# smartWatch_Basic_TOP.net
KiCad netlist of a schematic drawn in EAGLE
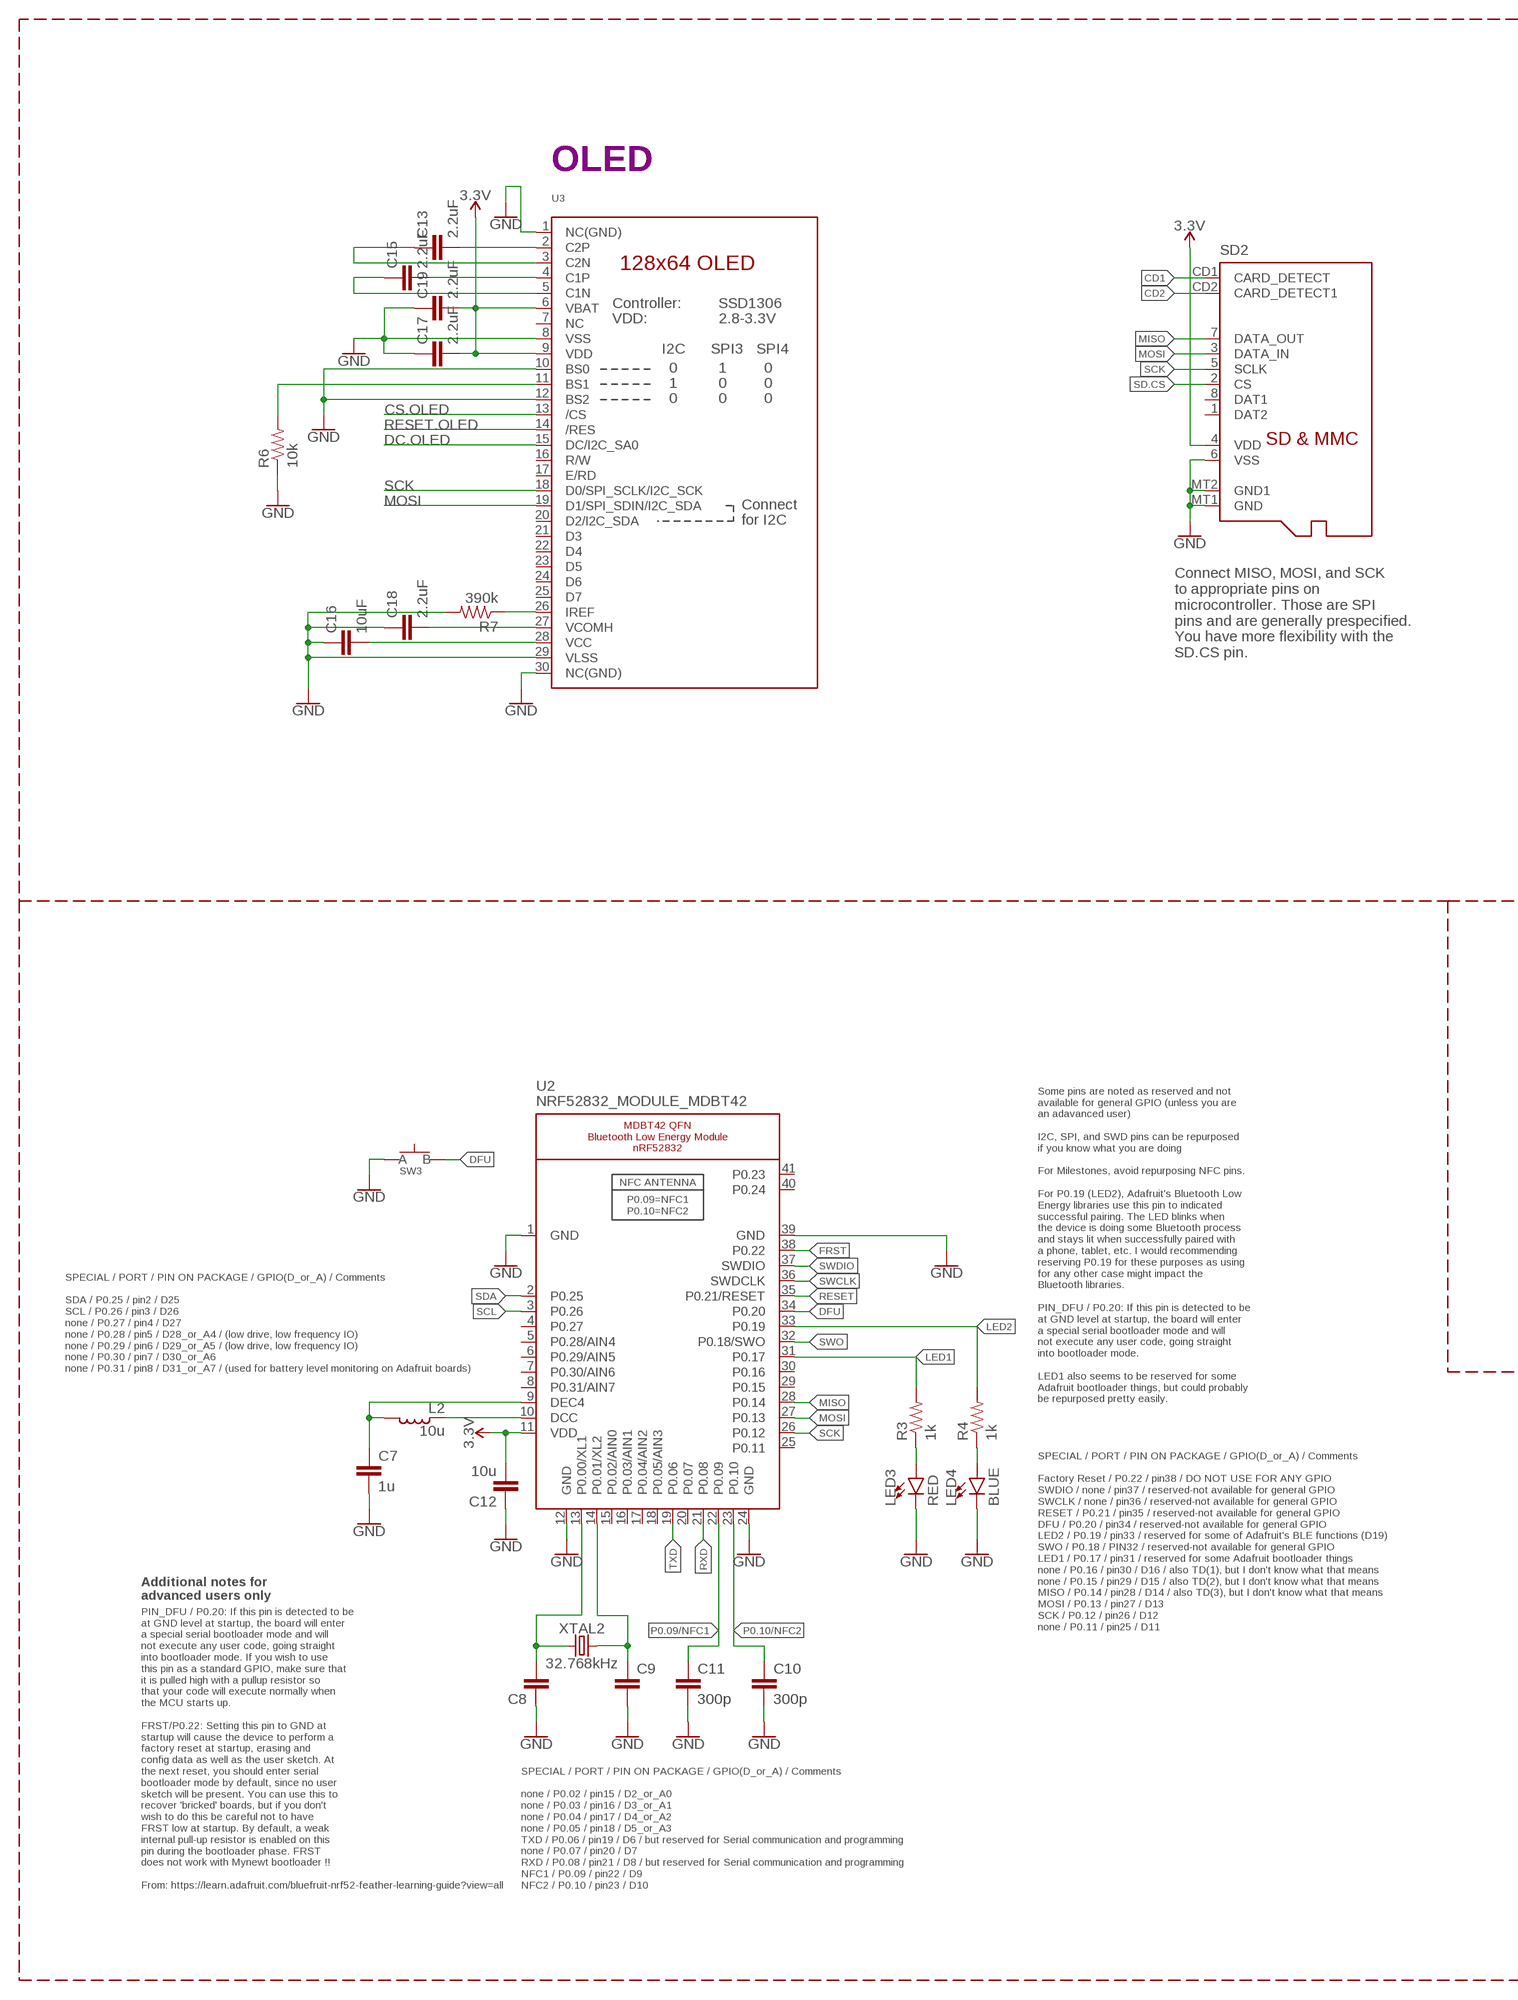
[diagram p0: schematic, sheet 1, part 1 of 2]
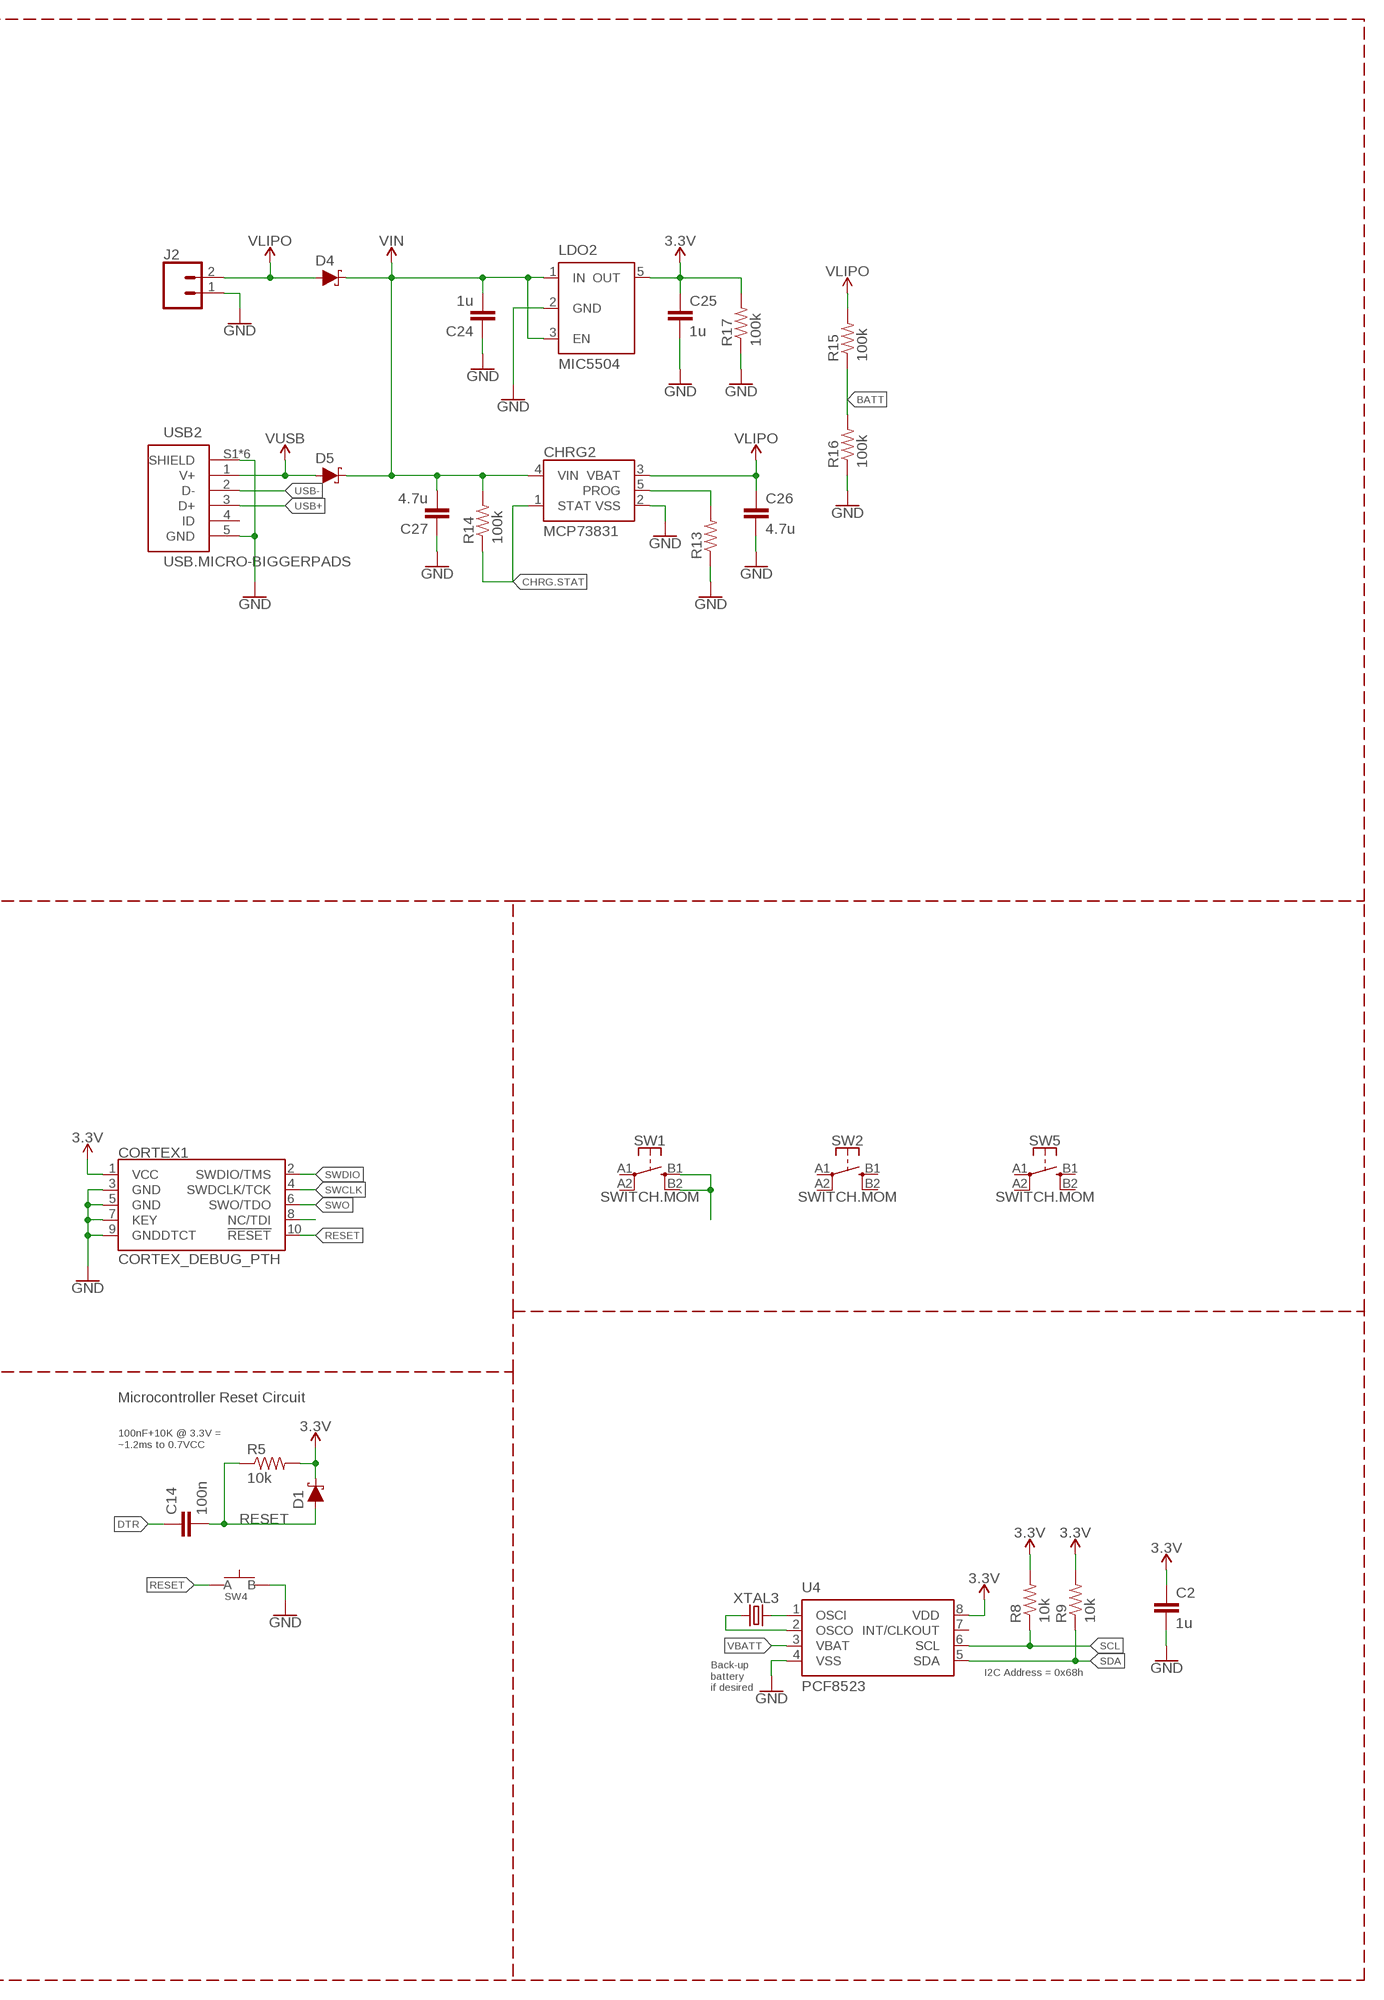
[diagram p1: schematic, sheet 1, part 2 of 2]

(export (version "E")
  (design (tool "Eeschema 10.0.6"))
  (components
    (comp (ref "C2")
      (value "1u")
      (footprint "eagle-import:C0603")
      (libsource (lib "eagle-import") (part "CAPACITOR0603"))
    )
    (comp (ref "C7")
      (value "1u")
      (footprint "eagle-import:C0603")
      (libsource (lib "eagle-import") (part "CAPACITOR0603"))
    )
    (comp (ref "C8")
      (value "CAPACITOR0603")
      (footprint "eagle-import:C0603")
      (libsource (lib "eagle-import") (part "CAPACITOR0603"))
    )
    (comp (ref "C9")
      (value "CAPACITOR0603")
      (footprint "eagle-import:C0603")
      (libsource (lib "eagle-import") (part "CAPACITOR0603"))
    )
    (comp (ref "C10")
      (value "300p")
      (footprint "eagle-import:C0603")
      (libsource (lib "eagle-import") (part "CAPACITOR0603"))
    )
    (comp (ref "C11")
      (value "300p")
      (footprint "eagle-import:C0603")
      (libsource (lib "eagle-import") (part "CAPACITOR0603"))
    )
    (comp (ref "C12")
      (value "10u")
      (footprint "eagle-import:C0805")
      (libsource (lib "eagle-import") (part "CAPACITOR0805"))
    )
    (comp (ref "C13")
      (value "2.2uF")
      (footprint "eagle-import:C0402")
      (libsource (lib "eagle-import") (part "CAPACITOR0402"))
    )
    (comp (ref "C14")
      (value "100n")
      (footprint "eagle-import:C0603")
      (libsource (lib "eagle-import") (part "CAPACITOR0603"))
    )
    (comp (ref "C15")
      (value "2.2uF")
      (footprint "eagle-import:C0402")
      (libsource (lib "eagle-import") (part "CAPACITOR0402"))
    )
    (comp (ref "C16")
      (value "10uF")
      (footprint "eagle-import:C0603")
      (libsource (lib "eagle-import") (part "CAPACITOR0603"))
    )
    (comp (ref "C17")
      (value "2.2uF")
      (footprint "eagle-import:C0402")
      (libsource (lib "eagle-import") (part "CAPACITOR0402"))
    )
    (comp (ref "C18")
      (value "2.2uF")
      (footprint "eagle-import:C0402")
      (libsource (lib "eagle-import") (part "CAPACITOR0402"))
    )
    (comp (ref "C19")
      (value "2.2uF")
      (footprint "eagle-import:C0402")
      (libsource (lib "eagle-import") (part "CAPACITOR0402"))
    )
    (comp (ref "C24")
      (value "1u")
      (footprint "eagle-import:C0603")
      (libsource (lib "eagle-import") (part "CAPACITOR0603"))
    )
    (comp (ref "C25")
      (value "1u")
      (footprint "eagle-import:C0603")
      (libsource (lib "eagle-import") (part "CAPACITOR0603"))
    )
    (comp (ref "C26")
      (value "4.7u")
      (footprint "eagle-import:C0603")
      (libsource (lib "eagle-import") (part "CAPACITOR0603"))
    )
    (comp (ref "C27")
      (value "4.7u")
      (footprint "eagle-import:C0603")
      (libsource (lib "eagle-import") (part "CAPACITOR0603"))
    )
    (comp (ref "CHRG2")
      (value "MCP73831")
      (footprint "eagle-import:SOT23-5")
      (libsource (lib "eagle-import") (part "MCP73831"))
    )
    (comp (ref "CORTEX1")
      (value "CORTEX_DEBUG_PTH")
      (footprint "eagle-import:2X5-PTH-1.27MM")
      (libsource (lib "eagle-import") (part "CORTEX_DEBUG_PTH"))
    )
    (comp (ref "D1")
      (value "SCHOTTKY-USC")
      (footprint "eagle-import:USC")
      (libsource (lib "eagle-import") (part "SCHOTTKY-USC"))
    )
    (comp (ref "D4")
      (value "SCHOTTKY-USC")
      (footprint "eagle-import:USC")
      (libsource (lib "eagle-import") (part "SCHOTTKY-USC"))
    )
    (comp (ref "D5")
      (value "SCHOTTKY-USC")
      (footprint "eagle-import:USC")
      (libsource (lib "eagle-import") (part "SCHOTTKY-USC"))
    )
    (comp (ref "J2")
      (value "CONN_02")
      (footprint "eagle-import:1X02")
      (libsource (lib "eagle-import") (part "CONN_02"))
    )
    (comp (ref "L2")
      (value "10u")
      (footprint "eagle-import:L0603")
      (libsource (lib "eagle-import") (part "INDUCTOR0603"))
    )
    (comp (ref "LDO2")
      (value "MIC5504")
      (footprint "eagle-import:SOT23-5")
      (libsource (lib "eagle-import") (part "MIC5504"))
    )
    (comp (ref "LED3")
      (value "RED")
      (footprint "eagle-import:LED-0603")
      (libsource (lib "eagle-import") (part "LED0603"))
    )
    (comp (ref "LED4")
      (value "BLUE")
      (footprint "eagle-import:LED-0603")
      (libsource (lib "eagle-import") (part "LED0603"))
    )
    (comp (ref "R3")
      (value "1k")
      (footprint "eagle-import:R0603")
      (libsource (lib "eagle-import") (part "RESISTOR0603"))
    )
    (comp (ref "R4")
      (value "1k")
      (footprint "eagle-import:R0603")
      (libsource (lib "eagle-import") (part "RESISTOR0603"))
    )
    (comp (ref "R5")
      (value "10k")
      (footprint "eagle-import:R0603")
      (libsource (lib "eagle-import") (part "RESISTOR0603"))
    )
    (comp (ref "R6")
      (value "10k")
      (footprint "eagle-import:R0603")
      (libsource (lib "eagle-import") (part "RESISTOR0603"))
    )
    (comp (ref "R7")
      (value "390k")
      (footprint "eagle-import:R0603")
      (libsource (lib "eagle-import") (part "RESISTOR0603"))
    )
    (comp (ref "R8")
      (value "10k")
      (footprint "eagle-import:R0603")
      (libsource (lib "eagle-import") (part "RESISTOR0603"))
    )
    (comp (ref "R9")
      (value "10k")
      (footprint "eagle-import:R0603")
      (libsource (lib "eagle-import") (part "RESISTOR0603"))
    )
    (comp (ref "R13")
      (value "RESISTOR0603")
      (footprint "eagle-import:R0603")
      (libsource (lib "eagle-import") (part "RESISTOR0603"))
    )
    (comp (ref "R14")
      (value "100k")
      (footprint "eagle-import:R0603")
      (libsource (lib "eagle-import") (part "RESISTOR0603"))
    )
    (comp (ref "R15")
      (value "100k")
      (footprint "eagle-import:R0603")
      (libsource (lib "eagle-import") (part "RESISTOR0603"))
    )
    (comp (ref "R16")
      (value "100k")
      (footprint "eagle-import:R0603")
      (libsource (lib "eagle-import") (part "RESISTOR0603"))
    )
    (comp (ref "R17")
      (value "100k")
      (footprint "eagle-import:R0603")
      (libsource (lib "eagle-import") (part "RESISTOR0603"))
    )
    (comp (ref "SD2")
      (value "MICROSD")
      (footprint "eagle-import:MICROSD")
      (libsource (lib "eagle-import") (part "MICROSD"))
    )
    (comp (ref "SW1")
      (value "SWITCH.MOM")
      (footprint "eagle-import:TACTILE_SWITCH_SMD_6.2MM_TALL")
      (libsource (lib "eagle-import") (part "SWITCH.MOM"))
    )
    (comp (ref "SW2")
      (value "SWITCH.MOM")
      (footprint "eagle-import:TACTILE_SWITCH_SMD_6.2MM_TALL")
      (libsource (lib "eagle-import") (part "SWITCH.MOM"))
    )
    (comp (ref "SW3")
      (value "SPST-PTS830GG140-COPY.1-3")
      (footprint "eagle-import:BUTTON-GULLWING")
      (libsource (lib "eagle-import") (part "SPST-PTS830GG140-COPY.1-3"))
    )
    (comp (ref "SW4")
      (value "SPST-PTS830GG140-COPY.1-3")
      (footprint "eagle-import:BUTTON-GULLWING")
      (libsource (lib "eagle-import") (part "SPST-PTS830GG140-COPY.1-3"))
    )
    (comp (ref "SW5")
      (value "SWITCH.MOM")
      (footprint "eagle-import:TACTILE_SWITCH_SMD_6.2MM_TALL")
      (libsource (lib "eagle-import") (part "SWITCH.MOM"))
    )
    (comp (ref "U2")
      (value "NRF52832_MODULE_MDBT42")
      (footprint "eagle-import:BLE_MODULE_RAYTAC_MDBT42")
      (libsource (lib "eagle-import") (part "NRF52832_MODULE_MDBT42"))
    )
    (comp (ref "U3")
      (value "DISP_OLED_UG-2864HSWEG01-NO-WRAPAROUND")
      (footprint "eagle-import:UG-2864HSWEG01_0.96IN_NO-WRAPAROUND")
      (libsource (lib "eagle-import") (part "DISP_OLED_UG-2864HSWEG01-NO-WRAPAROUND"))
    )
    (comp (ref "U4")
      (value "PCF8523")
      (footprint "eagle-import:SO8")
      (libsource (lib "eagle-import") (part "PCF8523"))
    )
    (comp (ref "USB2")
      (value "USB.MICRO-BIGGERPADS")
      (footprint "eagle-import:USB-MICRO-01.BIGGERPADS")
      (libsource (lib "eagle-import") (part "USB.MICRO-BIGGERPADS"))
    )
    (comp (ref "XTAL2")
      (value "32.768kHz")
      (footprint "eagle-import:2-SMD.NOLEAD.2.0MMTO1.2MM")
      (libsource (lib "eagle-import") (part "CRYSTALECS-.327-12.5-12-C-TR"))
    )
    (comp (ref "XTAL3")
      (value "32.7680kHz")
      (footprint "eagle-import:2-SMD.NOLEAD.2.0MMTO1.2MM")
      (fields (field (name "FREQ") "32.7680KHZ"))
      (libsource (lib "eagle-import") (part "CRYSTALECS-.327-12.5-12-C-TR"))
    )
  )
  (nets
    (net (code "1") (name "/CS.OLED") (class "Default")
      (node (ref "U3") (pin "13") (pinfunction "/CS_13") (pintype "input"))
    )
    (net (code "2") (name "/DC.OLED") (class "Default")
      (node (ref "U3") (pin "15") (pinfunction "DC/I2C_SA0_15") (pintype "input"))
    )
    (net (code "3") (name "/RESET.OLED") (class "Default")
      (node (ref "U3") (pin "14") (pinfunction "/RES_14") (pintype "input"))
    )
    (net (code "4") (name "3.3V") (class "Default")
      (node (ref "C12") (pin "2") (pinfunction "2_2") (pintype "passive"))
      (node (ref "C17") (pin "2") (pinfunction "2_2") (pintype "passive"))
      (node (ref "C19") (pin "2") (pinfunction "2_2") (pintype "passive"))
      (node (ref "C2") (pin "1") (pinfunction "1_1") (pintype "passive"))
      (node (ref "C25") (pin "1") (pinfunction "1_1") (pintype "passive"))
      (node (ref "CORTEX1") (pin "1") (pinfunction "VCC_1") (pintype "bidirectional"))
      (node (ref "D1") (pin "-") (pinfunction "C_-") (pintype "passive"))
      (node (ref "LDO2") (pin "5") (pinfunction "OUT_5") (pintype "bidirectional"))
      (node (ref "R17") (pin "2") (pinfunction "2_2") (pintype "passive"))
      (node (ref "R5") (pin "2") (pinfunction "2_2") (pintype "passive"))
      (node (ref "R8") (pin "2") (pinfunction "2_2") (pintype "passive"))
      (node (ref "R9") (pin "2") (pinfunction "2_2") (pintype "passive"))
      (node (ref "SD2") (pin "4") (pinfunction "VDD_4") (pintype "power_in"))
      (node (ref "U2") (pin "11") (pinfunction "VDD_11") (pintype "bidirectional"))
      (node (ref "U3") (pin "6") (pinfunction "VBAT_6") (pintype "input"))
      (node (ref "U3") (pin "9") (pinfunction "VDD_9") (pintype "power_in"))
      (node (ref "U4") (pin "8") (pinfunction "VDD_8") (pintype "power_in"))
    )
    (net (code "5") (name "BATT") (class "Default")
      (node (ref "R15") (pin "1") (pinfunction "1_1") (pintype "passive"))
      (node (ref "R16") (pin "2") (pinfunction "2_2") (pintype "passive"))
    )
    (net (code "6") (name "CD1") (class "Default")
      (node (ref "SD2") (pin "CD1") (pinfunction "CARD_DETECT_CD1") (pintype "passive"))
    )
    (net (code "7") (name "CD2") (class "Default")
      (node (ref "SD2") (pin "CD2") (pinfunction "CARD_DETECT1_CD2") (pintype "passive"))
    )
    (net (code "8") (name "CHRG.STAT") (class "Default")
      (node (ref "CHRG2") (pin "1") (pinfunction "STAT_1") (pintype "output"))
      (node (ref "R14") (pin "1") (pinfunction "1_1") (pintype "passive"))
    )
    (net (code "9") (name "DFU") (class "Default")
      (node (ref "SW3") (pin "3") (pinfunction "B_3") (pintype "bidirectional"))
      (node (ref "U2") (pin "34") (pinfunction "P0.20_34") (pintype "bidirectional"))
    )
    (net (code "10") (name "DTR") (class "Default")
      (node (ref "C14") (pin "1") (pinfunction "1_1") (pintype "passive"))
    )
    (net (code "11") (name "FRST") (class "Default")
      (node (ref "U2") (pin "38") (pinfunction "P0.22_38") (pintype "bidirectional"))
    )
    (net (code "12") (name "GND") (class "Default")
      (node (ref "C10") (pin "2") (pinfunction "2_2") (pintype "passive"))
      (node (ref "C11") (pin "2") (pinfunction "2_2") (pintype "passive"))
      (node (ref "C12") (pin "1") (pinfunction "1_1") (pintype "passive"))
      (node (ref "C16") (pin "1") (pinfunction "1_1") (pintype "passive"))
      (node (ref "C17") (pin "1") (pinfunction "1_1") (pintype "passive"))
      (node (ref "C18") (pin "1") (pinfunction "1_1") (pintype "passive"))
      (node (ref "C19") (pin "1") (pinfunction "1_1") (pintype "passive"))
      (node (ref "C2") (pin "2") (pinfunction "2_2") (pintype "passive"))
      (node (ref "C24") (pin "1") (pinfunction "1_1") (pintype "passive"))
      (node (ref "C25") (pin "2") (pinfunction "2_2") (pintype "passive"))
      (node (ref "C26") (pin "2") (pinfunction "2_2") (pintype "passive"))
      (node (ref "C27") (pin "1") (pinfunction "1_1") (pintype "passive"))
      (node (ref "C7") (pin "2") (pinfunction "2_2") (pintype "passive"))
      (node (ref "C8") (pin "1") (pinfunction "1_1") (pintype "passive"))
      (node (ref "C9") (pin "2") (pinfunction "2_2") (pintype "passive"))
      (node (ref "CHRG2") (pin "2") (pinfunction "VSS_2") (pintype "power_in"))
      (node (ref "CORTEX1") (pin "3") (pinfunction "GND_3") (pintype "bidirectional"))
      (node (ref "CORTEX1") (pin "5") (pinfunction "GND_5") (pintype "bidirectional"))
      (node (ref "CORTEX1") (pin "7") (pinfunction "KEY_7") (pintype "bidirectional"))
      (node (ref "CORTEX1") (pin "9") (pinfunction "GNDDTCT_9") (pintype "bidirectional"))
      (node (ref "J2") (pin "1") (pinfunction "1_1") (pintype "passive"))
      (node (ref "LDO2") (pin "2") (pinfunction "GND_2") (pintype "bidirectional"))
      (node (ref "LED3") (pin "C") (pinfunction "C_C") (pintype "passive"))
      (node (ref "LED4") (pin "C") (pinfunction "C_C") (pintype "passive"))
      (node (ref "R13") (pin "1") (pinfunction "1_1") (pintype "passive"))
      (node (ref "R16") (pin "1") (pinfunction "1_1") (pintype "passive"))
      (node (ref "R17") (pin "1") (pinfunction "1_1") (pintype "passive"))
      (node (ref "R6") (pin "1") (pinfunction "1_1") (pintype "passive"))
      (node (ref "R7") (pin "2") (pinfunction "2_2") (pintype "passive"))
      (node (ref "SD2") (pin "6") (pinfunction "VSS_6") (pintype "power_in"))
      (node (ref "SD2") (pin "MT1") (pinfunction "GND_MT1") (pintype "power_in"))
      (node (ref "SD2") (pin "MT2") (pinfunction "GND1_MT2") (pintype "power_in"))
      (node (ref "SW3") (pin "1") (pinfunction "A_1") (pintype "bidirectional"))
      (node (ref "SW4") (pin "3") (pinfunction "B_3") (pintype "bidirectional"))
      (node (ref "U2") (pin "1") (pinfunction "GND_1") (pintype "bidirectional"))
      (node (ref "U2") (pin "12") (pinfunction "GND_12") (pintype "bidirectional"))
      (node (ref "U2") (pin "24") (pinfunction "GND_24") (pintype "bidirectional"))
      (node (ref "U2") (pin "39") (pinfunction "GND_39") (pintype "bidirectional"))
      (node (ref "U3") (pin "1") (pinfunction "NC(GND)_1") (pintype "input"))
      (node (ref "U3") (pin "10") (pinfunction "BS0_10") (pintype "input"))
      (node (ref "U3") (pin "12") (pinfunction "BS2_12") (pintype "input"))
      (node (ref "U3") (pin "29") (pinfunction "VLSS_29") (pintype "power_in"))
      (node (ref "U3") (pin "30") (pinfunction "NC(GND)_30") (pintype "input"))
      (node (ref "U3") (pin "8") (pinfunction "VSS_8") (pintype "power_in"))
      (node (ref "U4") (pin "4") (pinfunction "VSS_4") (pintype "power_in"))
      (node (ref "USB2") (pin "5") (pinfunction "GND_5") (pintype "bidirectional"))
      (node (ref "USB2") (pin "S1") (pinfunction "SHIELD_S1") (pintype "bidirectional"))
      (node (ref "USB2") (pin "S2") (pinfunction "SHIELD_S2") (pintype "bidirectional"))
      (node (ref "USB2") (pin "S3") (pinfunction "SHIELD_S3") (pintype "bidirectional"))
      (node (ref "USB2") (pin "S4") (pinfunction "SHIELD_S4") (pintype "bidirectional"))
      (node (ref "USB2") (pin "S5") (pinfunction "SHIELD_S5") (pintype "bidirectional"))
      (node (ref "USB2") (pin "S6") (pinfunction "SHIELD_S6") (pintype "bidirectional"))
    )
    (net (code "13") (name "LED1") (class "Default")
      (node (ref "R3") (pin "2") (pinfunction "2_2") (pintype "passive"))
      (node (ref "U2") (pin "31") (pinfunction "P0.17_31") (pintype "bidirectional"))
    )
    (net (code "14") (name "LED2") (class "Default")
      (node (ref "R4") (pin "2") (pinfunction "2_2") (pintype "passive"))
      (node (ref "U2") (pin "33") (pinfunction "P0.19_33") (pintype "bidirectional"))
    )
    (net (code "15") (name "MISO") (class "Default")
      (node (ref "SD2") (pin "7") (pinfunction "DATA_OUT_7") (pintype "output"))
      (node (ref "U2") (pin "28") (pinfunction "P0.14_28") (pintype "bidirectional"))
    )
    (net (code "16") (name "MOSI") (class "Default")
      (node (ref "SD2") (pin "3") (pinfunction "DATA_IN_3") (pintype "input"))
      (node (ref "U2") (pin "27") (pinfunction "P0.13_27") (pintype "bidirectional"))
      (node (ref "U3") (pin "19") (pinfunction "D1/SPI_SDIN/I2C_SDA_19") (pintype "bidirectional"))
    )
    (net (code "17") (name "Net-(CHRG2-PROG)") (class "Default")
      (node (ref "CHRG2") (pin "5") (pinfunction "PROG_5") (pintype "input"))
      (node (ref "R13") (pin "2") (pinfunction "2_2") (pintype "passive"))
    )
    (net (code "18") (name "Net-(LED3-PadA)") (class "Default")
      (node (ref "LED3") (pin "A") (pinfunction "A_A") (pintype "passive"))
      (node (ref "R3") (pin "1") (pinfunction "1_1") (pintype "passive"))
    )
    (net (code "19") (name "Net-(LED4-PadA)") (class "Default")
      (node (ref "LED4") (pin "A") (pinfunction "A_A") (pintype "passive"))
      (node (ref "R4") (pin "1") (pinfunction "1_1") (pintype "passive"))
    )
    (net (code "20") (name "Net-(SW1-3)") (class "Default")
      (node (ref "SW1") (pin "B1") (pinfunction "3_B1") (pintype "passive"))
      (node (ref "SW1") (pin "B2") (pinfunction "4_B2") (pintype "passive"))
    )
    (net (code "21") (name "Net-(U2-DCC)") (class "Default")
      (node (ref "L2") (pin "1") (pinfunction "1_1") (pintype "passive"))
      (node (ref "U2") (pin "10") (pinfunction "DCC_10") (pintype "bidirectional"))
    )
    (net (code "22") (name "Net-(U2-DEC4)") (class "Default")
      (node (ref "C7") (pin "1") (pinfunction "1_1") (pintype "passive"))
      (node (ref "L2") (pin "2") (pinfunction "2_2") (pintype "passive"))
      (node (ref "U2") (pin "9") (pinfunction "DEC4_9") (pintype "bidirectional"))
    )
    (net (code "23") (name "Net-(U2-P0.00{slash}XL1)") (class "Default")
      (node (ref "C8") (pin "2") (pinfunction "2_2") (pintype "passive"))
      (node (ref "U2") (pin "13") (pinfunction "P0.00/XL1_13") (pintype "bidirectional"))
      (node (ref "XTAL2") (pin "P$1") (pinfunction "1_P$1") (pintype "passive"))
    )
    (net (code "24") (name "Net-(U2-P0.01{slash}XL2)") (class "Default")
      (node (ref "C9") (pin "1") (pinfunction "1_1") (pintype "passive"))
      (node (ref "U2") (pin "14") (pinfunction "P0.01/XL2_14") (pintype "bidirectional"))
      (node (ref "XTAL2") (pin "P$2") (pinfunction "2_P$2") (pintype "passive"))
    )
    (net (code "25") (name "Net-(U3-BS1)") (class "Default")
      (node (ref "R6") (pin "2") (pinfunction "2_2") (pintype "passive"))
      (node (ref "U3") (pin "11") (pinfunction "BS1_11") (pintype "input"))
    )
    (net (code "26") (name "Net-(U3-C1N)") (class "Default")
      (node (ref "C15") (pin "1") (pinfunction "1_1") (pintype "passive"))
      (node (ref "U3") (pin "5") (pinfunction "C1N_5") (pintype "input"))
    )
    (net (code "27") (name "Net-(U3-C1P)") (class "Default")
      (node (ref "C15") (pin "2") (pinfunction "2_2") (pintype "passive"))
      (node (ref "U3") (pin "4") (pinfunction "C1P_4") (pintype "input"))
    )
    (net (code "28") (name "Net-(U3-C2N)") (class "Default")
      (node (ref "C13") (pin "1") (pinfunction "1_1") (pintype "passive"))
      (node (ref "U3") (pin "3") (pinfunction "C2N_3") (pintype "input"))
    )
    (net (code "29") (name "Net-(U3-C2P)") (class "Default")
      (node (ref "C13") (pin "2") (pinfunction "2_2") (pintype "passive"))
      (node (ref "U3") (pin "2") (pinfunction "C2P_2") (pintype "input"))
    )
    (net (code "30") (name "Net-(U3-IREF)") (class "Default")
      (node (ref "R7") (pin "1") (pinfunction "1_1") (pintype "passive"))
      (node (ref "U3") (pin "26") (pinfunction "IREF_26") (pintype "input"))
    )
    (net (code "31") (name "Net-(U3-VCC)") (class "Default")
      (node (ref "C16") (pin "2") (pinfunction "2_2") (pintype "passive"))
      (node (ref "U3") (pin "28") (pinfunction "VCC_28") (pintype "power_in"))
    )
    (net (code "32") (name "Net-(U3-VCOMH)") (class "Default")
      (node (ref "C18") (pin "2") (pinfunction "2_2") (pintype "passive"))
      (node (ref "U3") (pin "27") (pinfunction "VCOMH_27") (pintype "output"))
    )
    (net (code "33") (name "Net-(U4-OSCI)") (class "Default")
      (node (ref "U4") (pin "1") (pinfunction "OSCI_1") (pintype "bidirectional"))
      (node (ref "XTAL3") (pin "P$2") (pinfunction "2_P$2") (pintype "passive"))
    )
    (net (code "34") (name "Net-(U4-OSCO)") (class "Default")
      (node (ref "U4") (pin "2") (pinfunction "OSCO_2") (pintype "bidirectional"))
      (node (ref "XTAL3") (pin "P$1") (pinfunction "1_P$1") (pintype "passive"))
    )
    (net (code "35") (name "P0.09{slash}NFC1") (class "Default")
      (node (ref "C11") (pin "1") (pinfunction "1_1") (pintype "passive"))
      (node (ref "U2") (pin "22") (pinfunction "P0.09_22") (pintype "bidirectional"))
    )
    (net (code "36") (name "P0.10{slash}NFC2") (class "Default")
      (node (ref "C10") (pin "1") (pinfunction "1_1") (pintype "passive"))
      (node (ref "U2") (pin "23") (pinfunction "P0.10_23") (pintype "bidirectional"))
    )
    (net (code "37") (name "RESET") (class "Default")
      (node (ref "C14") (pin "2") (pinfunction "2_2") (pintype "passive"))
      (node (ref "CORTEX1") (pin "10") (pinfunction "~{RESET}_10") (pintype "bidirectional"))
      (node (ref "D1") (pin "+") (pinfunction "A_+") (pintype "passive"))
      (node (ref "R5") (pin "1") (pinfunction "1_1") (pintype "passive"))
      (node (ref "SW4") (pin "1") (pinfunction "A_1") (pintype "bidirectional"))
      (node (ref "U2") (pin "35") (pinfunction "P0.21/RESET_35") (pintype "bidirectional"))
    )
    (net (code "38") (name "RXD") (class "Default")
      (node (ref "U2") (pin "21") (pinfunction "P0.08_21") (pintype "bidirectional"))
    )
    (net (code "39") (name "SCK") (class "Default")
      (node (ref "SD2") (pin "5") (pinfunction "SCLK_5") (pintype "input"))
      (node (ref "U2") (pin "26") (pinfunction "P0.12_26") (pintype "bidirectional"))
      (node (ref "U3") (pin "18") (pinfunction "D0/SPI_SCLK/I2C_SCK_18") (pintype "bidirectional"))
    )
    (net (code "40") (name "SCL") (class "Default")
      (node (ref "R8") (pin "1") (pinfunction "1_1") (pintype "passive"))
      (node (ref "U2") (pin "3") (pinfunction "P0.26_3") (pintype "bidirectional"))
      (node (ref "U4") (pin "6") (pinfunction "SCL_6") (pintype "bidirectional"))
    )
    (net (code "41") (name "SD.CS") (class "Default")
      (node (ref "SD2") (pin "2") (pinfunction "CS_2") (pintype "input"))
    )
    (net (code "42") (name "SDA") (class "Default")
      (node (ref "R9") (pin "1") (pinfunction "1_1") (pintype "passive"))
      (node (ref "U2") (pin "2") (pinfunction "P0.25_2") (pintype "bidirectional"))
      (node (ref "U4") (pin "5") (pinfunction "SDA_5") (pintype "bidirectional"))
    )
    (net (code "43") (name "SWCLK") (class "Default")
      (node (ref "CORTEX1") (pin "4") (pinfunction "SWDCLK/TCK_4") (pintype "bidirectional"))
      (node (ref "U2") (pin "36") (pinfunction "SWDCLK_36") (pintype "bidirectional"))
    )
    (net (code "44") (name "SWDIO") (class "Default")
      (node (ref "CORTEX1") (pin "2") (pinfunction "SWDIO/TMS_2") (pintype "bidirectional"))
      (node (ref "U2") (pin "37") (pinfunction "SWDIO_37") (pintype "bidirectional"))
    )
    (net (code "45") (name "SWO") (class "Default")
      (node (ref "CORTEX1") (pin "6") (pinfunction "SWO/TDO_6") (pintype "bidirectional"))
      (node (ref "U2") (pin "32") (pinfunction "P0.18/SWO_32") (pintype "bidirectional"))
    )
    (net (code "46") (name "TXD") (class "Default")
      (node (ref "U2") (pin "19") (pinfunction "P0.06_19") (pintype "bidirectional"))
    )
    (net (code "47") (name "USB+") (class "Default")
      (node (ref "USB2") (pin "3") (pinfunction "D+_3") (pintype "bidirectional"))
    )
    (net (code "48") (name "USB-") (class "Default")
      (node (ref "USB2") (pin "2") (pinfunction "D-_2") (pintype "bidirectional"))
    )
    (net (code "49") (name "VBATT") (class "Default")
      (node (ref "U4") (pin "3") (pinfunction "VBAT_3") (pintype "power_in"))
    )
    (net (code "50") (name "VIN") (class "Default")
      (node (ref "C24") (pin "2") (pinfunction "2_2") (pintype "passive"))
      (node (ref "C27") (pin "2") (pinfunction "2_2") (pintype "passive"))
      (node (ref "CHRG2") (pin "4") (pinfunction "VIN_4") (pintype "power_in"))
      (node (ref "D4") (pin "-") (pinfunction "C_-") (pintype "passive"))
      (node (ref "D5") (pin "-") (pinfunction "C_-") (pintype "passive"))
      (node (ref "LDO2") (pin "1") (pinfunction "IN_1") (pintype "bidirectional"))
      (node (ref "LDO2") (pin "3") (pinfunction "EN_3") (pintype "bidirectional"))
      (node (ref "R14") (pin "2") (pinfunction "2_2") (pintype "passive"))
    )
    (net (code "51") (name "VLIPO") (class "Default")
      (node (ref "C26") (pin "1") (pinfunction "1_1") (pintype "passive"))
      (node (ref "CHRG2") (pin "3") (pinfunction "VBAT_3") (pintype "power_in"))
      (node (ref "D4") (pin "+") (pinfunction "A_+") (pintype "passive"))
      (node (ref "J2") (pin "2") (pinfunction "2_2") (pintype "passive"))
      (node (ref "R15") (pin "2") (pinfunction "2_2") (pintype "passive"))
    )
    (net (code "52") (name "VUSB") (class "Default")
      (node (ref "D5") (pin "+") (pinfunction "A_+") (pintype "passive"))
      (node (ref "USB2") (pin "1") (pinfunction "V+_1") (pintype "bidirectional"))
    )
    (net (code "53") (name "unconnected-(CORTEX1-NC{slash}TDI-Pad8)") (class "Default")
      (node (ref "CORTEX1") (pin "8") (pinfunction "NC/TDI_8") (pintype "bidirectional"))
    )
    (net (code "54") (name "unconnected-(SD2-DAT1-Pad8)") (class "Default")
      (node (ref "SD2") (pin "8") (pinfunction "DAT1_8") (pintype "bidirectional"))
    )
    (net (code "55") (name "unconnected-(SD2-DAT2-Pad1)") (class "Default")
      (node (ref "SD2") (pin "1") (pinfunction "DAT2_1") (pintype "bidirectional"))
    )
    (net (code "56") (name "unconnected-(SW1-1-PadA1)") (class "Default")
      (node (ref "SW1") (pin "A1") (pinfunction "1_A1") (pintype "passive"))
    )
    (net (code "57") (name "unconnected-(SW1-2-PadA2)") (class "Default")
      (node (ref "SW1") (pin "A2") (pinfunction "2_A2") (pintype "passive"))
    )
    (net (code "58") (name "unconnected-(SW2-1-PadA1)") (class "Default")
      (node (ref "SW2") (pin "A1") (pinfunction "1_A1") (pintype "passive"))
    )
    (net (code "59") (name "unconnected-(SW2-2-PadA2)") (class "Default")
      (node (ref "SW2") (pin "A2") (pinfunction "2_A2") (pintype "passive"))
    )
    (net (code "60") (name "unconnected-(SW2-3-PadB1)") (class "Default")
      (node (ref "SW2") (pin "B1") (pinfunction "3_B1") (pintype "passive"))
    )
    (net (code "61") (name "unconnected-(SW2-4-PadB2)") (class "Default")
      (node (ref "SW2") (pin "B2") (pinfunction "4_B2") (pintype "passive"))
    )
    (net (code "62") (name "unconnected-(SW5-1-PadA1)") (class "Default")
      (node (ref "SW5") (pin "A1") (pinfunction "1_A1") (pintype "passive"))
    )
    (net (code "63") (name "unconnected-(SW5-2-PadA2)") (class "Default")
      (node (ref "SW5") (pin "A2") (pinfunction "2_A2") (pintype "passive"))
    )
    (net (code "64") (name "unconnected-(SW5-3-PadB1)") (class "Default")
      (node (ref "SW5") (pin "B1") (pinfunction "3_B1") (pintype "passive"))
    )
    (net (code "65") (name "unconnected-(SW5-4-PadB2)") (class "Default")
      (node (ref "SW5") (pin "B2") (pinfunction "4_B2") (pintype "passive"))
    )
    (net (code "66") (name "unconnected-(U2-P0.02{slash}AIN0-Pad15)") (class "Default")
      (node (ref "U2") (pin "15") (pinfunction "P0.02/AIN0_15") (pintype "bidirectional"))
    )
    (net (code "67") (name "unconnected-(U2-P0.03{slash}AIN1-Pad16)") (class "Default")
      (node (ref "U2") (pin "16") (pinfunction "P0.03/AIN1_16") (pintype "bidirectional"))
    )
    (net (code "68") (name "unconnected-(U2-P0.04{slash}AIN2-Pad17)") (class "Default")
      (node (ref "U2") (pin "17") (pinfunction "P0.04/AIN2_17") (pintype "bidirectional"))
    )
    (net (code "69") (name "unconnected-(U2-P0.05{slash}AIN3-Pad18)") (class "Default")
      (node (ref "U2") (pin "18") (pinfunction "P0.05/AIN3_18") (pintype "bidirectional"))
    )
    (net (code "70") (name "unconnected-(U2-P0.07-Pad20)") (class "Default")
      (node (ref "U2") (pin "20") (pinfunction "P0.07_20") (pintype "bidirectional"))
    )
    (net (code "71") (name "unconnected-(U2-P0.11-Pad25)") (class "Default")
      (node (ref "U2") (pin "25") (pinfunction "P0.11_25") (pintype "bidirectional"))
    )
    (net (code "72") (name "unconnected-(U2-P0.15-Pad29)") (class "Default")
      (node (ref "U2") (pin "29") (pinfunction "P0.15_29") (pintype "bidirectional"))
    )
    (net (code "73") (name "unconnected-(U2-P0.16-Pad30)") (class "Default")
      (node (ref "U2") (pin "30") (pinfunction "P0.16_30") (pintype "bidirectional"))
    )
    (net (code "74") (name "unconnected-(U2-P0.23-Pad41)") (class "Default")
      (node (ref "U2") (pin "41") (pinfunction "P0.23_41") (pintype "bidirectional"))
    )
    (net (code "75") (name "unconnected-(U2-P0.24-Pad40)") (class "Default")
      (node (ref "U2") (pin "40") (pinfunction "P0.24_40") (pintype "bidirectional"))
    )
    (net (code "76") (name "unconnected-(U2-P0.27-Pad4)") (class "Default")
      (node (ref "U2") (pin "4") (pinfunction "P0.27_4") (pintype "bidirectional"))
    )
    (net (code "77") (name "unconnected-(U2-P0.28{slash}AIN4-Pad5)") (class "Default")
      (node (ref "U2") (pin "5") (pinfunction "P0.28/AIN4_5") (pintype "bidirectional"))
    )
    (net (code "78") (name "unconnected-(U2-P0.29{slash}AIN5-Pad6)") (class "Default")
      (node (ref "U2") (pin "6") (pinfunction "P0.29/AIN5_6") (pintype "bidirectional"))
    )
    (net (code "79") (name "unconnected-(U2-P0.30{slash}AIN6-Pad7)") (class "Default")
      (node (ref "U2") (pin "7") (pinfunction "P0.30/AIN6_7") (pintype "bidirectional"))
    )
    (net (code "80") (name "unconnected-(U2-P0.31{slash}AIN7-Pad8)") (class "Default")
      (node (ref "U2") (pin "8") (pinfunction "P0.31/AIN7_8") (pintype "bidirectional"))
    )
    (net (code "81") (name "unconnected-(U3-D2{slash}I2C_SDA-Pad20)") (class "Default")
      (node (ref "U3") (pin "20") (pinfunction "D2/I2C_SDA_20") (pintype "bidirectional"))
    )
    (net (code "82") (name "unconnected-(U3-D3-Pad21)") (class "Default")
      (node (ref "U3") (pin "21") (pinfunction "D3_21") (pintype "bidirectional"))
    )
    (net (code "83") (name "unconnected-(U3-D4-Pad22)") (class "Default")
      (node (ref "U3") (pin "22") (pinfunction "D4_22") (pintype "bidirectional"))
    )
    (net (code "84") (name "unconnected-(U3-D5-Pad23)") (class "Default")
      (node (ref "U3") (pin "23") (pinfunction "D5_23") (pintype "bidirectional"))
    )
    (net (code "85") (name "unconnected-(U3-D6-Pad24)") (class "Default")
      (node (ref "U3") (pin "24") (pinfunction "D6_24") (pintype "bidirectional"))
    )
    (net (code "86") (name "unconnected-(U3-D7-Pad25)") (class "Default")
      (node (ref "U3") (pin "25") (pinfunction "D7_25") (pintype "bidirectional"))
    )
    (net (code "87") (name "unconnected-(U3-E{slash}RD-Pad17)") (class "Default")
      (node (ref "U3") (pin "17") (pinfunction "E/RD_17") (pintype "input"))
    )
    (net (code "88") (name "unconnected-(U3-NC-Pad7)") (class "Default")
      (node (ref "U3") (pin "7") (pinfunction "NC_7") (pintype "no_connect"))
    )
    (net (code "89") (name "unconnected-(U3-R{slash}W-Pad16)") (class "Default")
      (node (ref "U3") (pin "16") (pinfunction "R/W_16") (pintype "input"))
    )
    (net (code "90") (name "unconnected-(U4-INT{slash}CLKOUT-Pad7)") (class "Default")
      (node (ref "U4") (pin "7") (pinfunction "INT/CLKOUT_7") (pintype "bidirectional"))
    )
    (net (code "91") (name "unconnected-(USB2-ID-Pad4)") (class "Default")
      (node (ref "USB2") (pin "4") (pinfunction "ID_4") (pintype "bidirectional"))
    )
  )
)
